# Domino_Dual_Ethernet_No_Teardrop.net
KiCad netlist of a schematic drawn in EAGLE
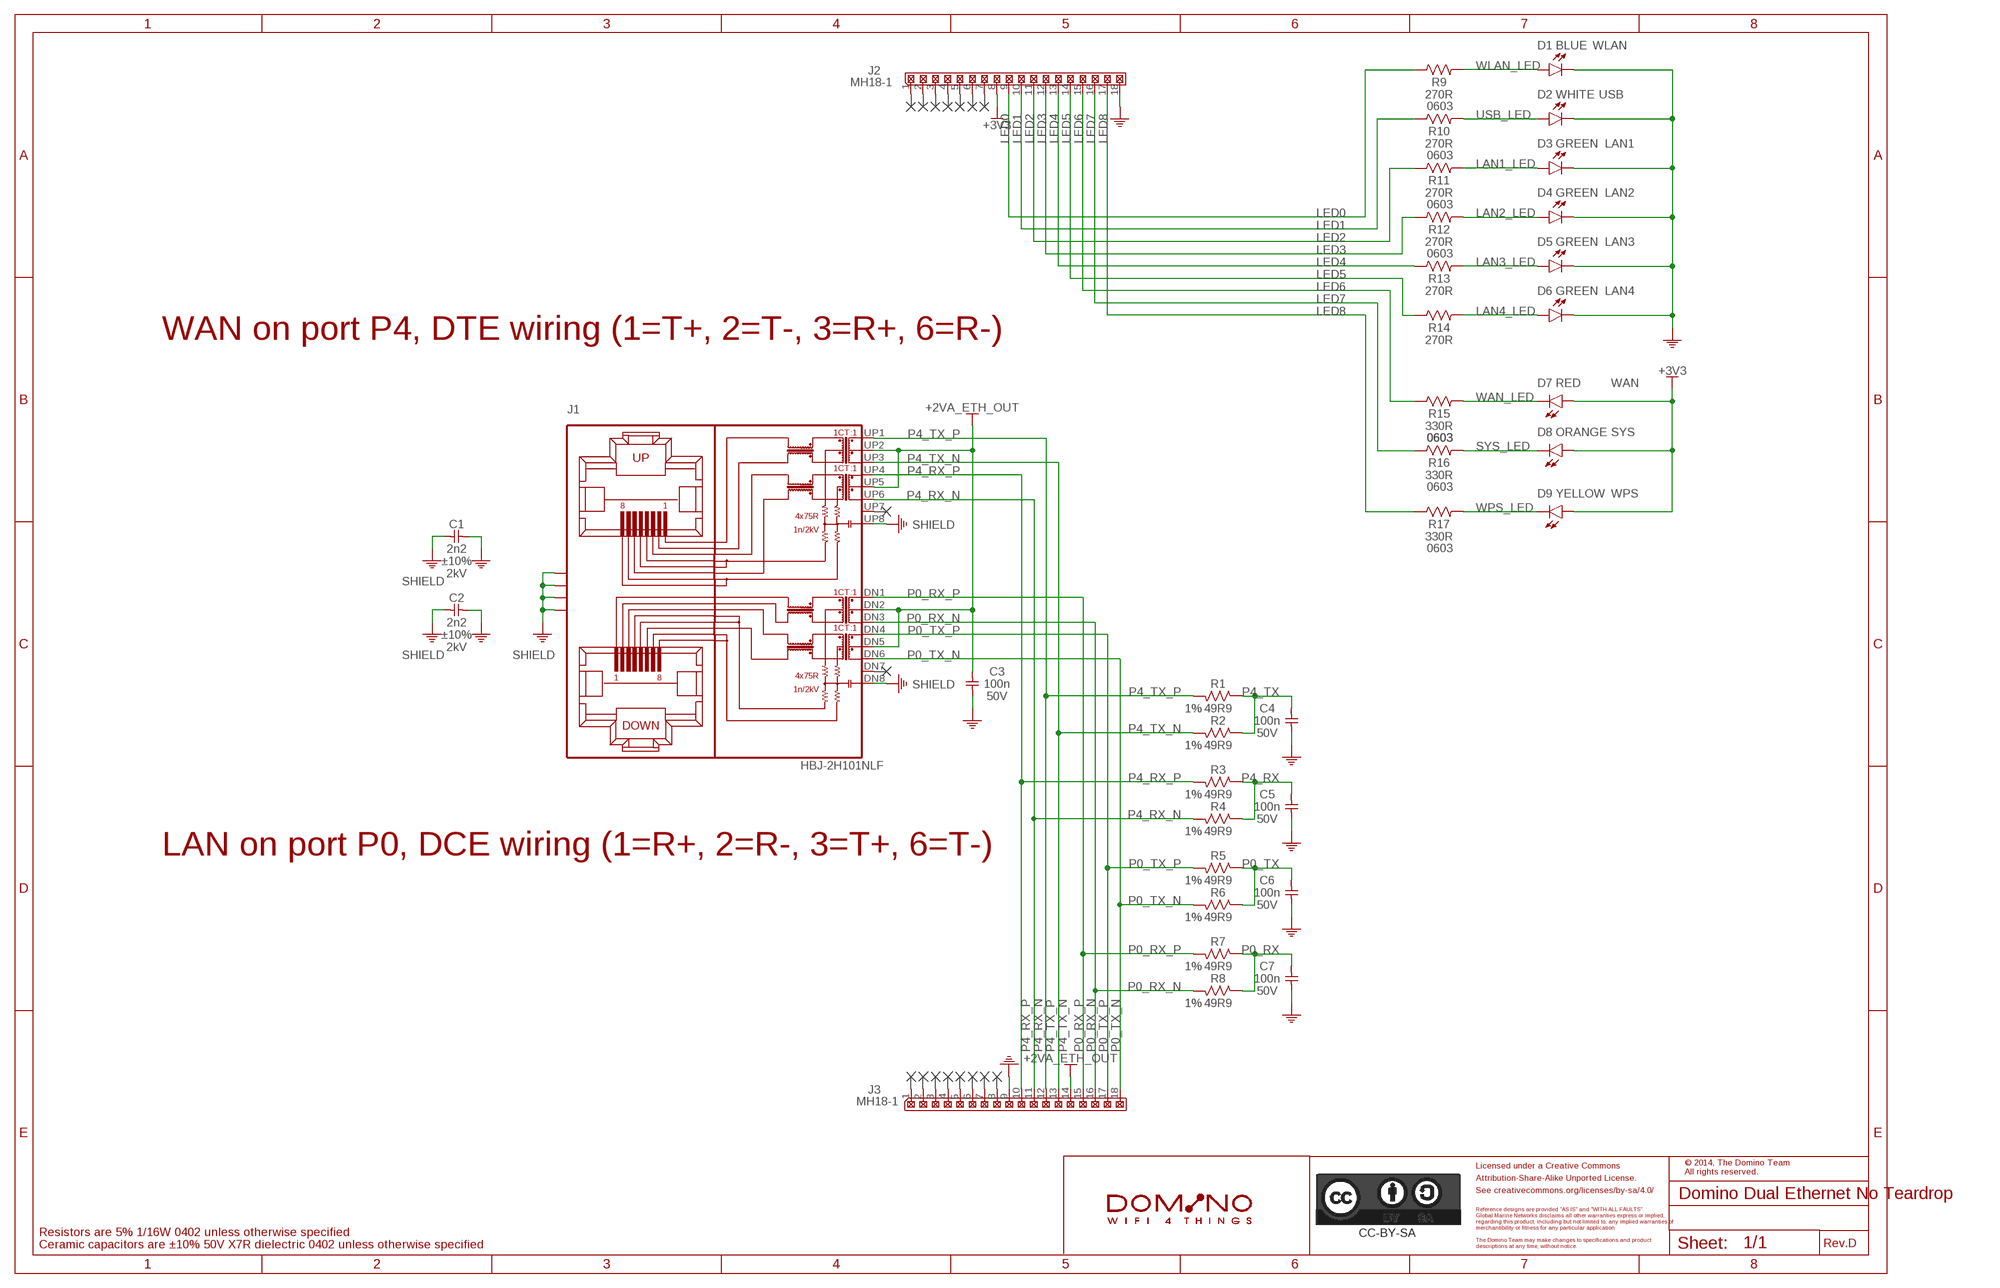
[diagram p0: schematic, sheet 1]

(export (version "E")
  (design (tool "Eeschema 10.0.6"))
  (components
    (comp (ref "C1")
      (value "2n2")
      (footprint "eagle-import:C1206")
      (fields
        (field (name "PARTNO") "C1210_2n2_X7R_10%_CER_2kV")
        (field (name "TOL") "±10%")
        (field (name "VOLT") "2kV")
      )
      (libsource (lib "eagle-import") (part "CAP_1206"))
    )
    (comp (ref "C2")
      (value "2n2")
      (footprint "eagle-import:C1206")
      (fields
        (field (name "PARTNO") "C1210_2n2_X7R_10%_CER_2kV")
        (field (name "TOL") "±10%")
        (field (name "VOLT") "2kV")
      )
      (libsource (lib "eagle-import") (part "CAP_1206"))
    )
    (comp (ref "C3")
      (value "100n")
      (footprint "eagle-import:C0402")
      (fields (field (name "PARTNO") "C0402_100n_X7R_10%_CER_50V") (field (name "VOLT") "50V"))
      (libsource (lib "eagle-import") (part "CAP_0402"))
    )
    (comp (ref "C4")
      (value "100n")
      (footprint "eagle-import:C0402")
      (fields (field (name "PARTNO") "C0402_100n_X7R_10%_CER_50V") (field (name "VOLT") "50V"))
      (libsource (lib "eagle-import") (part "CAP_0402"))
    )
    (comp (ref "C5")
      (value "100n")
      (footprint "eagle-import:C0402")
      (fields (field (name "PARTNO") "C0402_100n_X7R_10%_CER_50V") (field (name "VOLT") "50V"))
      (libsource (lib "eagle-import") (part "CAP_0402"))
    )
    (comp (ref "C6")
      (value "100n")
      (footprint "eagle-import:C0402")
      (fields (field (name "PARTNO") "C0402_100n_X7R_10%_CER_50V") (field (name "VOLT") "50V"))
      (libsource (lib "eagle-import") (part "CAP_0402"))
    )
    (comp (ref "C7")
      (value "100n")
      (footprint "eagle-import:C0402")
      (fields (field (name "PARTNO") "C0402_100n_X7R_10%_CER_50V") (field (name "VOLT") "50V"))
      (libsource (lib "eagle-import") (part "CAP_0402"))
    )
    (comp (ref "CC-BY-SA1")
      (value "CC-BY-SA_LOGO")
      (footprint "eagle-import:CC-BY-SA_LOGO")
      (libsource (lib "eagle-import") (part "CC-BY-SA_LOGO"))
    )
    (comp (ref "D1")
      (value "BLUE")
      (footprint "eagle-import:LED0603")
      (fields (field (name "PARTNO") "LED0603-BLUE"))
      (libsource (lib "eagle-import") (part "LED_0603"))
    )
    (comp (ref "D2")
      (value "WHITE")
      (footprint "eagle-import:LED0603")
      (fields (field (name "PARTNO") "LED0603-WHITE"))
      (libsource (lib "eagle-import") (part "LED_0603"))
    )
    (comp (ref "D3")
      (value "GREEN")
      (footprint "eagle-import:LED0603")
      (fields (field (name "PARTNO") "LED0603-GREEN"))
      (libsource (lib "eagle-import") (part "LED_0603"))
    )
    (comp (ref "D4")
      (value "GREEN")
      (footprint "eagle-import:LED0603")
      (fields (field (name "PARTNO") "LED0603-GREEN"))
      (libsource (lib "eagle-import") (part "LED_0603"))
    )
    (comp (ref "D5")
      (value "GREEN")
      (footprint "eagle-import:LED0603")
      (fields (field (name "PARTNO") "LED0603-GREEN"))
      (libsource (lib "eagle-import") (part "LED_0603"))
    )
    (comp (ref "D6")
      (value "GREEN")
      (footprint "eagle-import:LED0603")
      (fields (field (name "PARTNO") "LED0603-GREEN"))
      (libsource (lib "eagle-import") (part "LED_0603"))
    )
    (comp (ref "D7")
      (value "RED")
      (footprint "eagle-import:LED0603")
      (fields (field (name "PARTNO") "LED0603-ORANGE"))
      (libsource (lib "eagle-import") (part "LED_0603"))
    )
    (comp (ref "D8")
      (value "ORANGE")
      (footprint "eagle-import:LED0603")
      (fields (field (name "PARTNO") "LED0603-ORANGE"))
      (libsource (lib "eagle-import") (part "LED_0603"))
    )
    (comp (ref "D9")
      (value "YELLOW")
      (footprint "eagle-import:LED0603")
      (fields (field (name "PARTNO") "LED0603-YELLOW"))
      (libsource (lib "eagle-import") (part "LED_0603"))
    )
    (comp (ref "J1")
      (value "HBJ-2H101NLF")
      (footprint "eagle-import:HBJ-2H101NLF")
      (libsource (lib "eagle-import") (part "HBJ-2H101NLF"))
    )
    (comp (ref "J2")
      (value "MH18-1")
      (footprint "eagle-import:MH18-1-0.1")
      (fields (field (name "PARTNO") "MH18-1-0.1"))
      (libsource (lib "eagle-import") (part "MH18-1"))
    )
    (comp (ref "J3")
      (value "MH18-1")
      (footprint "eagle-import:MH18-1-0.1")
      (fields (field (name "PARTNO") "MH18-1-0.1"))
      (libsource (lib "eagle-import") (part "MH18-1"))
    )
    (comp (ref "R1")
      (value "49R9")
      (footprint "eagle-import:R0402")
      (fields (field (name "PARTNO") "R0402_49R9_1%_62.5mW") (field (name "TOL") "1%"))
      (libsource (lib "eagle-import") (part "RES_0402"))
    )
    (comp (ref "R2")
      (value "49R9")
      (footprint "eagle-import:R0402")
      (fields (field (name "PARTNO") "R0402_49R9_1%_62.5mW") (field (name "TOL") "1%"))
      (libsource (lib "eagle-import") (part "RES_0402"))
    )
    (comp (ref "R3")
      (value "49R9")
      (footprint "eagle-import:R0402")
      (fields (field (name "PARTNO") "R0402_49R9_1%_62.5mW") (field (name "TOL") "1%"))
      (libsource (lib "eagle-import") (part "RES_0402"))
    )
    (comp (ref "R4")
      (value "49R9")
      (footprint "eagle-import:R0402")
      (fields (field (name "PARTNO") "R0402_49R9_1%_62.5mW") (field (name "TOL") "1%"))
      (libsource (lib "eagle-import") (part "RES_0402"))
    )
    (comp (ref "R5")
      (value "49R9")
      (footprint "eagle-import:R0402")
      (fields (field (name "PARTNO") "R0402_49R9_1%_62.5mW") (field (name "TOL") "1%"))
      (libsource (lib "eagle-import") (part "RES_0402"))
    )
    (comp (ref "R6")
      (value "49R9")
      (footprint "eagle-import:R0402")
      (fields (field (name "PARTNO") "R0402_49R9_1%_62.5mW") (field (name "TOL") "1%"))
      (libsource (lib "eagle-import") (part "RES_0402"))
    )
    (comp (ref "R7")
      (value "49R9")
      (footprint "eagle-import:R0402")
      (fields (field (name "PARTNO") "R0402_49R9_1%_62.5mW") (field (name "TOL") "1%"))
      (libsource (lib "eagle-import") (part "RES_0402"))
    )
    (comp (ref "R8")
      (value "49R9")
      (footprint "eagle-import:R0402")
      (fields (field (name "PARTNO") "R0402_49R9_1%_62.5mW") (field (name "TOL") "1%"))
      (libsource (lib "eagle-import") (part "RES_0402"))
    )
    (comp (ref "R9")
      (value "270R")
      (footprint "eagle-import:R0603")
      (fields (field (name "SIZE") "0603") (field (name "PARTNO") "R0603_270R_5%_125mW"))
      (libsource (lib "eagle-import") (part "RES_0603"))
    )
    (comp (ref "R10")
      (value "270R")
      (footprint "eagle-import:R0603")
      (fields (field (name "SIZE") "0603") (field (name "PARTNO") "R0603_270R_5%_125mW"))
      (libsource (lib "eagle-import") (part "RES_0603"))
    )
    (comp (ref "R11")
      (value "270R")
      (footprint "eagle-import:R0603")
      (fields (field (name "SIZE") "0603") (field (name "PARTNO") "R0603_270R_5%_125mW"))
      (libsource (lib "eagle-import") (part "RES_0603"))
    )
    (comp (ref "R12")
      (value "270R")
      (footprint "eagle-import:R0603")
      (fields (field (name "SIZE") "0603") (field (name "PARTNO") "R0603_270R_5%_125mW"))
      (libsource (lib "eagle-import") (part "RES_0603"))
    )
    (comp (ref "R13")
      (value "270R")
      (footprint "eagle-import:R0603")
      (fields (field (name "PARTNO") "R0603_270R_5%_125mW"))
      (libsource (lib "eagle-import") (part "RES_0603"))
    )
    (comp (ref "R14")
      (value "270R")
      (footprint "eagle-import:R0603")
      (fields (field (name "SIZE") "0603") (field (name "PARTNO") "R0603_270R_5%_125mW"))
      (libsource (lib "eagle-import") (part "RES_0603"))
    )
    (comp (ref "R15")
      (value "330R")
      (footprint "eagle-import:R0603")
      (fields (field (name "SIZE") "0603") (field (name "PARTNO") "R0603_330R_5%_125mW"))
      (libsource (lib "eagle-import") (part "RES_0603"))
    )
    (comp (ref "R16")
      (value "330R")
      (footprint "eagle-import:R0603")
      (fields (field (name "SIZE") "0603") (field (name "PARTNO") "R0603_330R_5%_125mW"))
      (libsource (lib "eagle-import") (part "RES_0603"))
    )
    (comp (ref "R17")
      (value "330R")
      (footprint "eagle-import:R0603")
      (fields (field (name "SIZE") "0603") (field (name "PARTNO") "R0603_330R_5%_125mW"))
      (libsource (lib "eagle-import") (part "RES_0603"))
    )
    (comp (ref "U$10")
      (value "DOMINO_LOGO")
      (footprint "eagle-import:DOMINO_LOGO")
      (libsource (lib "eagle-import") (part "DOMINO_LOGO"))
    )
  )
  (nets
    (net (code "1") (name "+2VA_ETH_OUT") (class "Default")
      (node (ref "C3") (pin "2") (pinfunction "2_2") (pintype "passive"))
      (node (ref "J1") (pin "DN2") (pinfunction "DR2_DN2") (pintype "passive"))
      (node (ref "J1") (pin "DN5") (pinfunction "DR5_DN5") (pintype "passive"))
      (node (ref "J1") (pin "UP2") (pinfunction "UR2_UP2") (pintype "passive"))
      (node (ref "J1") (pin "UP5") (pinfunction "UR5_UP5") (pintype "passive"))
      (node (ref "J3") (pin "14") (pinfunction "14_14") (pintype "passive"))
    )
    (net (code "2") (name "+3V3") (class "Default")
      (node (ref "D7") (pin "2") (pinfunction "A_2") (pintype "passive"))
      (node (ref "D8") (pin "2") (pinfunction "A_2") (pintype "passive"))
      (node (ref "D9") (pin "2") (pinfunction "A_2") (pintype "passive"))
      (node (ref "J2") (pin "8") (pinfunction "8_8") (pintype "passive"))
    )
    (net (code "3") (name "/LAN1_LED") (class "Default")
      (node (ref "D3") (pin "2") (pinfunction "A_2") (pintype "passive"))
      (node (ref "R11") (pin "2") (pinfunction "2_2") (pintype "passive"))
    )
    (net (code "4") (name "/LAN2_LED") (class "Default")
      (node (ref "D4") (pin "2") (pinfunction "A_2") (pintype "passive"))
      (node (ref "R12") (pin "2") (pinfunction "2_2") (pintype "passive"))
    )
    (net (code "5") (name "/LAN3_LED") (class "Default")
      (node (ref "D5") (pin "2") (pinfunction "A_2") (pintype "passive"))
      (node (ref "R13") (pin "2") (pinfunction "2_2") (pintype "passive"))
    )
    (net (code "6") (name "/LAN4_LED") (class "Default")
      (node (ref "D6") (pin "2") (pinfunction "A_2") (pintype "passive"))
      (node (ref "R14") (pin "2") (pinfunction "2_2") (pintype "passive"))
    )
    (net (code "7") (name "/LED0") (class "Default")
      (node (ref "J2") (pin "9") (pinfunction "9_9") (pintype "passive"))
      (node (ref "R9") (pin "1") (pinfunction "1_1") (pintype "passive"))
    )
    (net (code "8") (name "/LED1") (class "Default")
      (node (ref "J2") (pin "10") (pinfunction "10_10") (pintype "passive"))
      (node (ref "R10") (pin "1") (pinfunction "1_1") (pintype "passive"))
    )
    (net (code "9") (name "/LED2") (class "Default")
      (node (ref "J2") (pin "11") (pinfunction "11_11") (pintype "passive"))
      (node (ref "R11") (pin "1") (pinfunction "1_1") (pintype "passive"))
    )
    (net (code "10") (name "/LED3") (class "Default")
      (node (ref "J2") (pin "12") (pinfunction "12_12") (pintype "passive"))
      (node (ref "R12") (pin "1") (pinfunction "1_1") (pintype "passive"))
    )
    (net (code "11") (name "/LED4") (class "Default")
      (node (ref "J2") (pin "13") (pinfunction "13_13") (pintype "passive"))
      (node (ref "R13") (pin "1") (pinfunction "1_1") (pintype "passive"))
    )
    (net (code "12") (name "/LED5") (class "Default")
      (node (ref "J2") (pin "14") (pinfunction "14_14") (pintype "passive"))
      (node (ref "R14") (pin "1") (pinfunction "1_1") (pintype "passive"))
    )
    (net (code "13") (name "/LED6") (class "Default")
      (node (ref "J2") (pin "15") (pinfunction "15_15") (pintype "passive"))
      (node (ref "R15") (pin "1") (pinfunction "1_1") (pintype "passive"))
    )
    (net (code "14") (name "/LED7") (class "Default")
      (node (ref "J2") (pin "16") (pinfunction "16_16") (pintype "passive"))
      (node (ref "R16") (pin "1") (pinfunction "1_1") (pintype "passive"))
    )
    (net (code "15") (name "/LED8") (class "Default")
      (node (ref "J2") (pin "17") (pinfunction "17_17") (pintype "passive"))
      (node (ref "R17") (pin "1") (pinfunction "1_1") (pintype "passive"))
    )
    (net (code "16") (name "/P0_RX") (class "Default")
      (node (ref "C7") (pin "2") (pinfunction "2_2") (pintype "passive"))
      (node (ref "R7") (pin "1") (pinfunction "1_1") (pintype "passive"))
      (node (ref "R8") (pin "1") (pinfunction "1_1") (pintype "passive"))
    )
    (net (code "17") (name "/P0_RX_N") (class "Default")
      (node (ref "J1") (pin "DN3") (pinfunction "DR3_DN3") (pintype "passive"))
      (node (ref "J3") (pin "16") (pinfunction "16_16") (pintype "passive"))
      (node (ref "R8") (pin "2") (pinfunction "2_2") (pintype "passive"))
    )
    (net (code "18") (name "/P0_RX_P") (class "Default")
      (node (ref "J1") (pin "DN1") (pinfunction "DR1_DN1") (pintype "passive"))
      (node (ref "J3") (pin "15") (pinfunction "15_15") (pintype "passive"))
      (node (ref "R7") (pin "2") (pinfunction "2_2") (pintype "passive"))
    )
    (net (code "19") (name "/P0_TX") (class "Default")
      (node (ref "C6") (pin "2") (pinfunction "2_2") (pintype "passive"))
      (node (ref "R5") (pin "1") (pinfunction "1_1") (pintype "passive"))
      (node (ref "R6") (pin "1") (pinfunction "1_1") (pintype "passive"))
    )
    (net (code "20") (name "/P0_TX_N") (class "Default")
      (node (ref "J1") (pin "DN6") (pinfunction "DR6_DN6") (pintype "passive"))
      (node (ref "J3") (pin "18") (pinfunction "18_18") (pintype "passive"))
      (node (ref "R6") (pin "2") (pinfunction "2_2") (pintype "passive"))
    )
    (net (code "21") (name "/P0_TX_P") (class "Default")
      (node (ref "J1") (pin "DN4") (pinfunction "DR4_DN4") (pintype "passive"))
      (node (ref "J3") (pin "17") (pinfunction "17_17") (pintype "passive"))
      (node (ref "R5") (pin "2") (pinfunction "2_2") (pintype "passive"))
    )
    (net (code "22") (name "/P4_RX") (class "Default")
      (node (ref "C5") (pin "2") (pinfunction "2_2") (pintype "passive"))
      (node (ref "R3") (pin "1") (pinfunction "1_1") (pintype "passive"))
      (node (ref "R4") (pin "1") (pinfunction "1_1") (pintype "passive"))
    )
    (net (code "23") (name "/P4_RX_N") (class "Default")
      (node (ref "J1") (pin "UP6") (pinfunction "UR6_UP6") (pintype "passive"))
      (node (ref "J3") (pin "11") (pinfunction "11_11") (pintype "passive"))
      (node (ref "R4") (pin "2") (pinfunction "2_2") (pintype "passive"))
    )
    (net (code "24") (name "/P4_RX_P") (class "Default")
      (node (ref "J1") (pin "UP4") (pinfunction "UR4_UP4") (pintype "passive"))
      (node (ref "J3") (pin "10") (pinfunction "10_10") (pintype "passive"))
      (node (ref "R3") (pin "2") (pinfunction "2_2") (pintype "passive"))
    )
    (net (code "25") (name "/P4_TX") (class "Default")
      (node (ref "C4") (pin "2") (pinfunction "2_2") (pintype "passive"))
      (node (ref "R1") (pin "1") (pinfunction "1_1") (pintype "passive"))
      (node (ref "R2") (pin "1") (pinfunction "1_1") (pintype "passive"))
    )
    (net (code "26") (name "/P4_TX_N") (class "Default")
      (node (ref "J1") (pin "UP3") (pinfunction "UR3_UP3") (pintype "passive"))
      (node (ref "J3") (pin "13") (pinfunction "13_13") (pintype "passive"))
      (node (ref "R2") (pin "2") (pinfunction "2_2") (pintype "passive"))
    )
    (net (code "27") (name "/P4_TX_P") (class "Default")
      (node (ref "J1") (pin "UP1") (pinfunction "UR1_UP1") (pintype "passive"))
      (node (ref "J3") (pin "12") (pinfunction "12_12") (pintype "passive"))
      (node (ref "R1") (pin "2") (pinfunction "2_2") (pintype "passive"))
    )
    (net (code "28") (name "/SYS_LED") (class "Default")
      (node (ref "D8") (pin "1") (pinfunction "C_1") (pintype "passive"))
      (node (ref "R16") (pin "2") (pinfunction "2_2") (pintype "passive"))
    )
    (net (code "29") (name "/USB_LED") (class "Default")
      (node (ref "D2") (pin "2") (pinfunction "A_2") (pintype "passive"))
      (node (ref "R10") (pin "2") (pinfunction "2_2") (pintype "passive"))
    )
    (net (code "30") (name "/WAN_LED") (class "Default")
      (node (ref "D7") (pin "1") (pinfunction "C_1") (pintype "passive"))
      (node (ref "R15") (pin "2") (pinfunction "2_2") (pintype "passive"))
    )
    (net (code "31") (name "/WLAN_LED") (class "Default")
      (node (ref "D1") (pin "2") (pinfunction "A_2") (pintype "passive"))
      (node (ref "R9") (pin "2") (pinfunction "2_2") (pintype "passive"))
    )
    (net (code "32") (name "/WPS_LED") (class "Default")
      (node (ref "D9") (pin "1") (pinfunction "C_1") (pintype "passive"))
      (node (ref "R17") (pin "2") (pinfunction "2_2") (pintype "passive"))
    )
    (net (code "33") (name "GND") (class "Default")
      (node (ref "C1") (pin "1") (pinfunction "1_1") (pintype "passive"))
      (node (ref "C2") (pin "1") (pinfunction "1_1") (pintype "passive"))
      (node (ref "C3") (pin "1") (pinfunction "1_1") (pintype "passive"))
      (node (ref "C4") (pin "1") (pinfunction "1_1") (pintype "passive"))
      (node (ref "C5") (pin "1") (pinfunction "1_1") (pintype "passive"))
      (node (ref "C6") (pin "1") (pinfunction "1_1") (pintype "passive"))
      (node (ref "C7") (pin "1") (pinfunction "1_1") (pintype "passive"))
      (node (ref "D1") (pin "1") (pinfunction "C_1") (pintype "passive"))
      (node (ref "D2") (pin "1") (pinfunction "C_1") (pintype "passive"))
      (node (ref "D3") (pin "1") (pinfunction "C_1") (pintype "passive"))
      (node (ref "D4") (pin "1") (pinfunction "C_1") (pintype "passive"))
      (node (ref "D5") (pin "1") (pinfunction "C_1") (pintype "passive"))
      (node (ref "D6") (pin "1") (pinfunction "C_1") (pintype "passive"))
      (node (ref "J2") (pin "18") (pinfunction "18_18") (pintype "passive"))
      (node (ref "J3") (pin "9") (pinfunction "9_9") (pintype "passive"))
    )
    (net (code "34") (name "SHIELD") (class "Default")
      (node (ref "C1") (pin "2") (pinfunction "2_2") (pintype "passive"))
      (node (ref "C2") (pin "2") (pinfunction "2_2") (pintype "passive"))
      (node (ref "J1") (pin "DN8") (pinfunction "DR8_DN8") (pintype "power_in"))
      (node (ref "J1") (pin "P$1") (pinfunction "SHIELD_P$1") (pintype "power_in"))
      (node (ref "J1") (pin "P$2") (pinfunction "SHIELD_P$2") (pintype "power_in"))
      (node (ref "J1") (pin "P$3") (pinfunction "SHIELD_P$3") (pintype "power_in"))
      (node (ref "J1") (pin "P$4") (pinfunction "SHIELD_P$4") (pintype "power_in"))
      (node (ref "J1") (pin "UP8") (pinfunction "UR8_UP8") (pintype "power_in"))
    )
    (net (code "35") (name "unconnected-(J1-DR7-PadDN7)") (class "Default")
      (node (ref "J1") (pin "DN7") (pinfunction "DR7_DN7") (pintype "no_connect"))
    )
    (net (code "36") (name "unconnected-(J1-UR7-PadUP7)") (class "Default")
      (node (ref "J1") (pin "UP7") (pinfunction "UR7_UP7") (pintype "no_connect"))
    )
    (net (code "37") (name "unconnected-(J2-Pad1)") (class "Default")
      (node (ref "J2") (pin "1") (pinfunction "1_1") (pintype "passive"))
    )
    (net (code "38") (name "unconnected-(J2-Pad2)") (class "Default")
      (node (ref "J2") (pin "2") (pinfunction "2_2") (pintype "passive"))
    )
    (net (code "39") (name "unconnected-(J2-Pad3)") (class "Default")
      (node (ref "J2") (pin "3") (pinfunction "3_3") (pintype "passive"))
    )
    (net (code "40") (name "unconnected-(J2-Pad4)") (class "Default")
      (node (ref "J2") (pin "4") (pinfunction "4_4") (pintype "passive"))
    )
    (net (code "41") (name "unconnected-(J2-Pad5)") (class "Default")
      (node (ref "J2") (pin "5") (pinfunction "5_5") (pintype "passive"))
    )
    (net (code "42") (name "unconnected-(J2-Pad6)") (class "Default")
      (node (ref "J2") (pin "6") (pinfunction "6_6") (pintype "passive"))
    )
    (net (code "43") (name "unconnected-(J2-Pad7)") (class "Default")
      (node (ref "J2") (pin "7") (pinfunction "7_7") (pintype "passive"))
    )
    (net (code "44") (name "unconnected-(J3-Pad1)") (class "Default")
      (node (ref "J3") (pin "1") (pinfunction "1_1") (pintype "passive"))
    )
    (net (code "45") (name "unconnected-(J3-Pad2)") (class "Default")
      (node (ref "J3") (pin "2") (pinfunction "2_2") (pintype "passive"))
    )
    (net (code "46") (name "unconnected-(J3-Pad3)") (class "Default")
      (node (ref "J3") (pin "3") (pinfunction "3_3") (pintype "passive"))
    )
    (net (code "47") (name "unconnected-(J3-Pad4)") (class "Default")
      (node (ref "J3") (pin "4") (pinfunction "4_4") (pintype "passive"))
    )
    (net (code "48") (name "unconnected-(J3-Pad5)") (class "Default")
      (node (ref "J3") (pin "5") (pinfunction "5_5") (pintype "passive"))
    )
    (net (code "49") (name "unconnected-(J3-Pad6)") (class "Default")
      (node (ref "J3") (pin "6") (pinfunction "6_6") (pintype "passive"))
    )
    (net (code "50") (name "unconnected-(J3-Pad7)") (class "Default")
      (node (ref "J3") (pin "7") (pinfunction "7_7") (pintype "passive"))
    )
    (net (code "51") (name "unconnected-(J3-Pad8)") (class "Default")
      (node (ref "J3") (pin "8") (pinfunction "8_8") (pintype "passive"))
    )
  )
)
